# IMU.net
KiCad netlist of a schematic drawn in Altium Designer
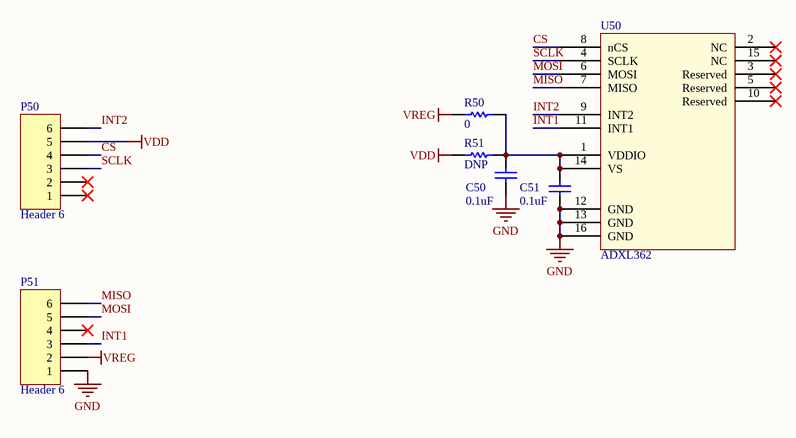
[diagram p0: IMU.SchDoc]

(export (version "E")
  (design (tool "Eeschema 10.0.6"))
  (components
    (comp (ref "C50")
      (value "0.1uF")
      (footprint "0402")
      (description "CAP CER 100nF/0.1UF 10V X5R 0402")
      (fields
        (field (name "DIGI-KEY PART NUMBER") "1276-1022-1-ND")
        (field (name "MANUFACTURER") "Samsung Electro-Mechanics")
      )
      (libsource (lib "WISP6") (part "C-0.1uF-10V-X5R-0402"))
    )
    (comp (ref "C51")
      (value "0.1uF")
      (footprint "0402")
      (description "CAP CER 100nF/0.1UF 10V X5R 0402")
      (fields
        (field (name "DIGI-KEY PART NUMBER") "1276-1022-1-ND")
        (field (name "MANUFACTURER") "Samsung Electro-Mechanics")
      )
      (libsource (lib "WISP6") (part "C-0.1uF-10V-X5R-0402"))
    )
    (comp (ref "P50")
      (value "Header 6")
      (footprint "HDR1X6")
      (description "Header, 6-Pin")
      (fields (field (name "PUBLISHER") "Altium Limited"))
      (libsource (lib "Miscellaneous Connectors") (part "Header 6"))
    )
    (comp (ref "P51")
      (value "Header 6")
      (footprint "HDR1X6")
      (description "Header, 6-Pin")
      (fields (field (name "PUBLISHER") "Altium Limited"))
      (libsource (lib "Miscellaneous Connectors") (part "Header 6"))
    )
    (comp (ref "R50")
      (value "0")
      (footprint "0402")
      (description "RES 0 OHM JUMPER 1/16W 0402")
      (fields
        (field (name "MANUFACTURER") "YAGEO")
        (field (name "MANUFACTURER PART NUMBER") "RC0402JR-070RL")
      )
      (libsource (lib "WISP6") (part "R-0-0.063W-*-0402"))
    )
    (comp (ref "R51")
      (value "DNP")
      (footprint "0402")
      (description "Chip Resistor (Surface Mount)")
      (fields (field (name "Comment") "Generic resistor"))
      (libsource (lib "WISP6") (part "res"))
    )
    (comp (ref "U50")
      (value "ADXL362")
      (footprint "ADXL362")
      (description "Analog Devices low power accelerometer")
      (fields
        (field (name "MANUFACTURER") "Analog Devices Inc.")
        (field (name "MANUFACTURER PART NUMBER") "ADXL362BCCZ-RL")
      )
      (libsource (lib "WISP6") (part "ADXL362"))
    )
  )
  (nets
    (net (code "1") (name "/CS") (class "Default")
      (node (ref "P50") (pin "4") (pinfunction "4_4") (pintype "passive"))
      (node (ref "U50") (pin "8") (pinfunction "nCS_8") (pintype "passive"))
    )
    (net (code "2") (name "/INT1") (class "Default")
      (node (ref "P51") (pin "3") (pinfunction "3_3") (pintype "passive"))
      (node (ref "U50") (pin "11") (pinfunction "INT1_11") (pintype "passive"))
    )
    (net (code "3") (name "/INT2") (class "Default")
      (node (ref "P50") (pin "6") (pinfunction "6_6") (pintype "passive"))
      (node (ref "U50") (pin "9") (pinfunction "INT2_9") (pintype "passive"))
    )
    (net (code "4") (name "/MISO") (class "Default")
      (node (ref "P51") (pin "6") (pinfunction "6_6") (pintype "passive"))
      (node (ref "U50") (pin "7") (pinfunction "MISO_7") (pintype "passive"))
    )
    (net (code "5") (name "/MOSI") (class "Default")
      (node (ref "P51") (pin "5") (pinfunction "5_5") (pintype "passive"))
      (node (ref "U50") (pin "6") (pinfunction "MOSI_6") (pintype "passive"))
    )
    (net (code "6") (name "/SCLK") (class "Default")
      (node (ref "P50") (pin "3") (pinfunction "3_3") (pintype "passive"))
      (node (ref "U50") (pin "4") (pinfunction "SCLK_4") (pintype "passive"))
    )
    (net (code "7") (name "GND") (class "Default")
      (node (ref "C50") (pin "1") (pinfunction "1_1") (pintype "passive"))
      (node (ref "C51") (pin "1") (pinfunction "1_1") (pintype "passive"))
      (node (ref "P51") (pin "1") (pinfunction "1_1") (pintype "passive"))
      (node (ref "U50") (pin "12") (pinfunction "GND_12") (pintype "passive"))
      (node (ref "U50") (pin "13") (pinfunction "GND_13") (pintype "passive"))
      (node (ref "U50") (pin "16") (pinfunction "GND_16") (pintype "passive"))
    )
    (net (code "8") (name "Net-(U50-VDDIO)") (class "Default")
      (node (ref "C50") (pin "2") (pinfunction "2_2") (pintype "passive"))
      (node (ref "C51") (pin "2") (pinfunction "2_2") (pintype "passive"))
      (node (ref "R50") (pin "2") (pinfunction "2_2") (pintype "passive"))
      (node (ref "R51") (pin "2") (pinfunction "2_2") (pintype "passive"))
      (node (ref "U50") (pin "1") (pinfunction "VDDIO_1") (pintype "passive"))
      (node (ref "U50") (pin "14") (pinfunction "VS_14") (pintype "passive"))
    )
    (net (code "9") (name "VDD") (class "Default")
      (node (ref "P50") (pin "5") (pinfunction "5_5") (pintype "passive"))
      (node (ref "R51") (pin "1") (pinfunction "1_1") (pintype "passive"))
    )
    (net (code "10") (name "VREG") (class "Default")
      (node (ref "P51") (pin "2") (pinfunction "2_2") (pintype "passive"))
      (node (ref "R50") (pin "1") (pinfunction "1_1") (pintype "passive"))
    )
    (net (code "11") (name "unconnected-(P50-Pad1)") (class "Default")
      (node (ref "P50") (pin "1") (pinfunction "1_1") (pintype "passive+no_connect"))
    )
    (net (code "12") (name "unconnected-(P50-Pad2)") (class "Default")
      (node (ref "P50") (pin "2") (pinfunction "2_2") (pintype "passive+no_connect"))
    )
    (net (code "13") (name "unconnected-(P51-Pad4)") (class "Default")
      (node (ref "P51") (pin "4") (pinfunction "4_4") (pintype "passive+no_connect"))
    )
    (net (code "14") (name "unconnected-(U50-NC-Pad2)") (class "Default")
      (node (ref "U50") (pin "2") (pinfunction "NC_2") (pintype "passive+no_connect"))
    )
    (net (code "15") (name "unconnected-(U50-NC-Pad15)") (class "Default")
      (node (ref "U50") (pin "15") (pinfunction "NC_15") (pintype "passive+no_connect"))
    )
    (net (code "16") (name "unconnected-(U50-Reserved-Pad3)") (class "Default")
      (node (ref "U50") (pin "3") (pinfunction "Reserved_3") (pintype "passive+no_connect"))
    )
    (net (code "17") (name "unconnected-(U50-Reserved-Pad5)") (class "Default")
      (node (ref "U50") (pin "5") (pinfunction "Reserved_5") (pintype "passive+no_connect"))
    )
    (net (code "18") (name "unconnected-(U50-Reserved-Pad10)") (class "Default")
      (node (ref "U50") (pin "10") (pinfunction "Reserved_10") (pintype "passive+no_connect"))
    )
  )
)
